# Impedance_Measurement_System.net
KiCad netlist of a schematic drawn in EAGLE
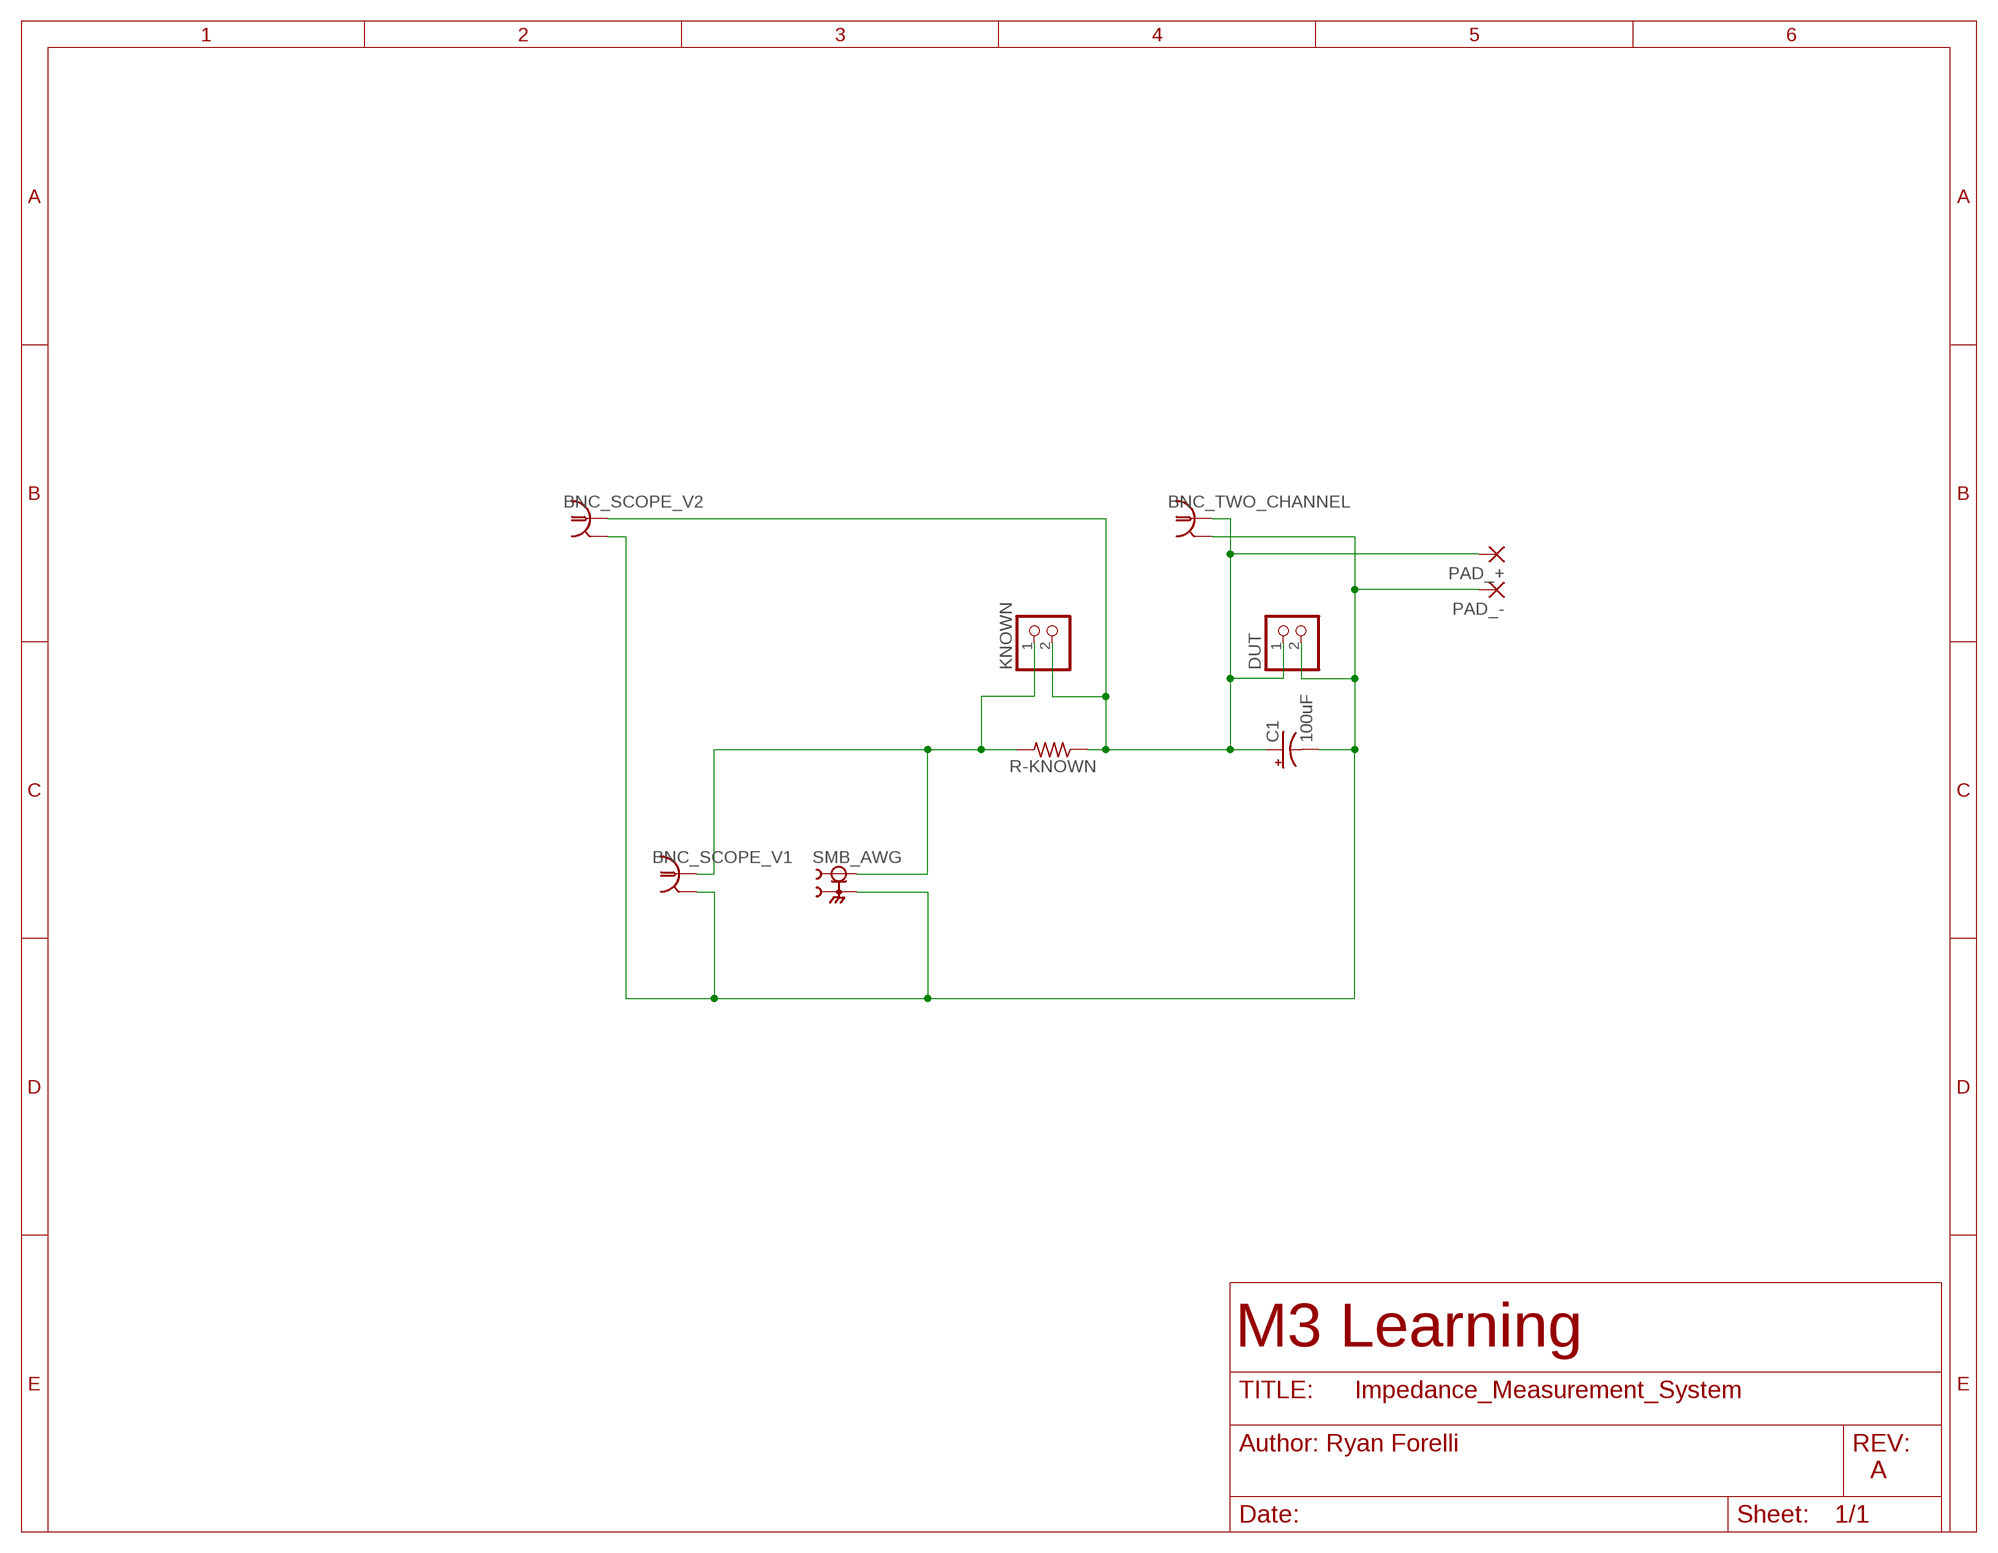
[diagram p0: schematic, sheet 1]

(export (version "E")
  (design (tool "Eeschema 10.0.6"))
  (components
    (comp (ref "BNC_SCOPE_V1")
      (value "112404")
      (footprint "eagle-import:112404")
      (fields (field (name "MF") "Amphenol RF"))
      (libsource (lib "eagle-import") (part "112404"))
    )
    (comp (ref "BNC_SCOPE_V2")
      (value "112404")
      (footprint "eagle-import:112404")
      (fields (field (name "MF") "Amphenol RF"))
      (libsource (lib "eagle-import") (part "112404"))
    )
    (comp (ref "BNC_TWO_CHANNEL")
      (value "112404")
      (footprint "eagle-import:112404")
      (fields (field (name "MF") "Amphenol RF"))
      (libsource (lib "eagle-import") (part "112404"))
    )
    (comp (ref "C1")
      (value "100uF")
      (footprint "eagle-import:CPOL-RADIAL-2.5MM-5MM")
      (libsource (lib "eagle-import") (part "10UF-POLAR-RADIAL-2.5MM-25V-20%"))
    )
    (comp (ref "DUT")
      (value "PINHD-1X2")
      (footprint "eagle-import:1X02")
      (libsource (lib "eagle-import") (part "PINHD-1X2"))
    )
    (comp (ref "KNOWN")
      (value "PINHD-1X2")
      (footprint "eagle-import:1X02")
      (libsource (lib "eagle-import") (part "PINHD-1X2"))
    )
    (comp (ref "PAD_+")
      (value "SMD5")
      (footprint "eagle-import:SMD2,54-5,08")
      (libsource (lib "eagle-import") (part "SMD5"))
    )
    (comp (ref "PAD_-")
      (value "SMD5")
      (footprint "eagle-import:SMD2,54-5,08")
      (libsource (lib "eagle-import") (part "SMD5"))
    )
    (comp (ref "R-KNOWN")
      (value "10K")
      (footprint "eagle-import:0204_7")
      (libsource (lib "eagle-import") (part "R-US_0204/7"))
    )
    (comp (ref "SMB_AWG")
      (value "CONSMB006-G")
      (footprint "eagle-import:LINX_CONSMB006-G")
      (fields (field (name "MF") "Linx Technologies Inc."))
      (libsource (lib "eagle-import") (part "CONSMB006-G"))
    )
  )
  (nets
    (net (code "1") (name "Net-(BNC_SCOPE_V1-Pad1)") (class "Default")
      (node (ref "BNC_SCOPE_V1") (pin "1") (pinfunction "1_1") (pintype "passive"))
      (node (ref "KNOWN") (pin "1") (pinfunction "1_1") (pintype "passive"))
      (node (ref "R-KNOWN") (pin "2") (pinfunction "2_2") (pintype "passive"))
      (node (ref "SMB_AWG") (pin "1") (pinfunction "1_1") (pintype "passive"))
    )
    (net (code "2") (name "Net-(C1-+)") (class "Default")
      (node (ref "BNC_SCOPE_V2") (pin "1") (pinfunction "1_1") (pintype "passive"))
      (node (ref "BNC_TWO_CHANNEL") (pin "1") (pinfunction "1_1") (pintype "passive"))
      (node (ref "C1") (pin "1") (pinfunction "+_1") (pintype "passive"))
      (node (ref "DUT") (pin "1") (pinfunction "1_1") (pintype "passive"))
      (node (ref "KNOWN") (pin "2") (pinfunction "2_2") (pintype "passive"))
      (node (ref "PAD_+") (pin "1") (pinfunction "P_1") (pintype "passive"))
      (node (ref "R-KNOWN") (pin "1") (pinfunction "1_1") (pintype "passive"))
    )
    (net (code "3") (name "Net-(C1--)") (class "Default")
      (node (ref "BNC_SCOPE_V1") (pin "2") (pinfunction "2_2") (pintype "passive"))
      (node (ref "BNC_SCOPE_V1") (pin "3") (pinfunction "2_3") (pintype "passive"))
      (node (ref "BNC_SCOPE_V1") (pin "4") (pinfunction "2_4") (pintype "passive"))
      (node (ref "BNC_SCOPE_V1") (pin "5") (pinfunction "2_5") (pintype "passive"))
      (node (ref "BNC_SCOPE_V2") (pin "2") (pinfunction "2_2") (pintype "passive"))
      (node (ref "BNC_SCOPE_V2") (pin "3") (pinfunction "2_3") (pintype "passive"))
      (node (ref "BNC_SCOPE_V2") (pin "4") (pinfunction "2_4") (pintype "passive"))
      (node (ref "BNC_SCOPE_V2") (pin "5") (pinfunction "2_5") (pintype "passive"))
      (node (ref "BNC_TWO_CHANNEL") (pin "2") (pinfunction "2_2") (pintype "passive"))
      (node (ref "BNC_TWO_CHANNEL") (pin "3") (pinfunction "2_3") (pintype "passive"))
      (node (ref "BNC_TWO_CHANNEL") (pin "4") (pinfunction "2_4") (pintype "passive"))
      (node (ref "BNC_TWO_CHANNEL") (pin "5") (pinfunction "2_5") (pintype "passive"))
      (node (ref "C1") (pin "2") (pinfunction "-_2") (pintype "passive"))
      (node (ref "DUT") (pin "2") (pinfunction "2_2") (pintype "passive"))
      (node (ref "PAD_-") (pin "1") (pinfunction "P_1") (pintype "passive"))
      (node (ref "SMB_AWG") (pin "G1") (pinfunction "2_G1") (pintype "passive"))
      (node (ref "SMB_AWG") (pin "G2") (pinfunction "2_G2") (pintype "passive"))
      (node (ref "SMB_AWG") (pin "G3") (pinfunction "2_G3") (pintype "passive"))
      (node (ref "SMB_AWG") (pin "G4") (pinfunction "2_G4") (pintype "passive"))
    )
  )
)
